# simplefocmini_2022-04-20.net
KiCad netlist of a schematic drawn in Altium Designer
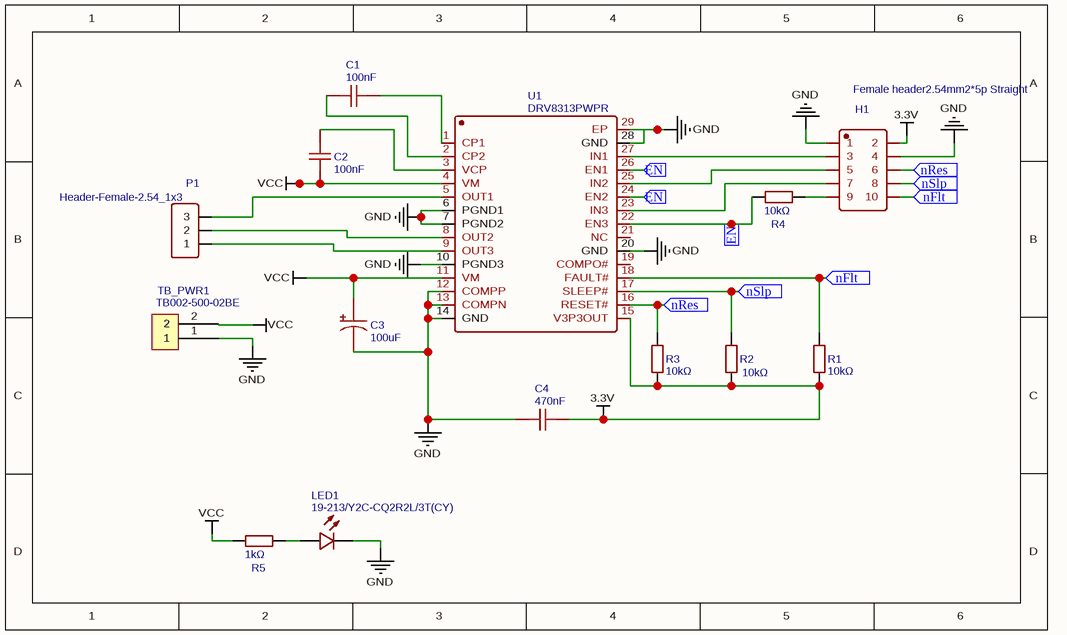
[diagram p0: simplefocmini_2022-04-20.schdoc]

(export (version "E")
  (design (tool "Eeschema 10.0.6"))
  (components
    (comp (ref "C1")
      (value "100nF")
      (fields
        (field (name "BOM_MANUFACTURER PART") "CL10B104KB8NNNC")
        (field (name "BOM_SUPPLIER PART") "C1591")
      )
      (libsource (lib "altium-import") (part "root_0_100nF_"))
    )
    (comp (ref "C2")
      (value "100nF")
      (fields
        (field (name "BOM_MANUFACTURER PART") "CL10B104KB8NNNC")
        (field (name "BOM_SUPPLIER PART") "C1591")
      )
      (libsource (lib "altium-import") (part "root_1_100nF_"))
    )
    (comp (ref "C3")
      (value "100uF")
      (fields
        (field (name "BOM_SUPPLIER PART") "C294520")
        (field (name "BOM_MANUFACTURER PART") "VT1V101M-CRE77")
        (field (name "CONTRIBUTOR") "LCSC")
      )
      (libsource (lib "altium-import") (part "root_0_100uF_"))
    )
    (comp (ref "C4")
      (value "470nF")
      (fields
        (field (name "BOM_SUPPLIER PART") "C327269")
        (field (name "BOM_MANUFACTURER PART") "CC0603ZRY5V6BB474")
        (field (name "CONTRIBUTOR") "LCSC")
      )
      (libsource (lib "altium-import") (part "root_0_470nF_"))
    )
    (comp (ref "H1")
      (value "Female header2.54mm2*5p Straight")
      (fields (field (name "BOM_SUPPLIER PART") "C30419"))
      (libsource (lib "altium-import") (part "root_0_Female header2.54mm2*5p Straight_"))
    )
    (comp (ref "LED1")
      (value "19-213/Y2C-CQ2R2L/3T(CY)")
      (fields (field (name "BOM_SUPPLIER PART") "C72038"))
      (libsource (lib "altium-import") (part "root_0_19-213/Y2C-CQ2R2L/3T(CY)_"))
    )
    (comp (ref "P1")
      (value "Header-Female-2.54_1x3")
      (fields (field (name "BOM_SUPPLIER PART") "C146243"))
      (libsource (lib "altium-import") (part "root_2_Header-Female-2.54_1x3_"))
    )
    (comp (ref "R1")
      (value "10kΩ")
      (fields
        (field (name "BOM_MANUFACTURER PART") "0603WAF4701T5E")
        (field (name "BOM_SUPPLIER PART") "C23162")
      )
      (libsource (lib "altium-import") (part "root_1_10kΩ_"))
    )
    (comp (ref "R2")
      (value "10kΩ")
      (fields
        (field (name "BOM_MANUFACTURER PART") "0603WAF4701T5E")
        (field (name "BOM_SUPPLIER PART") "C23162")
      )
      (libsource (lib "altium-import") (part "root_1_10kΩ_"))
    )
    (comp (ref "R3")
      (value "10kΩ")
      (fields
        (field (name "BOM_MANUFACTURER PART") "0603WAF4701T5E")
        (field (name "BOM_SUPPLIER PART") "C23162")
      )
      (libsource (lib "altium-import") (part "root_1_10kΩ_"))
    )
    (comp (ref "R4")
      (value "10kΩ")
      (fields
        (field (name "BOM_MANUFACTURER PART") "0603WAF4701T5E")
        (field (name "BOM_SUPPLIER PART") "C23162")
      )
      (libsource (lib "altium-import") (part "root_0_10kΩ_"))
    )
    (comp (ref "R5")
      (value "1kΩ")
      (fields
        (field (name "BOM_MANUFACTURER PART") "0603WAF4701T5E")
        (field (name "BOM_SUPPLIER PART") "C23162")
      )
      (libsource (lib "altium-import") (part "root_0_1kΩ_"))
    )
    (comp (ref "TB_PWR1")
      (value "TB002-500-02BE")
      (fields (field (name "CONTRIBUTOR") "the.skuric"))
      (libsource (lib "altium-import") (part "root_0_TB002-500-02BE_"))
    )
    (comp (ref "U1")
      (value "DRV8313PWPR")
      (fields (field (name "BOM_SUPPLIER PART") "C92482") (field (name "CONTRIBUTOR") "LCSC"))
      (libsource (lib "altium-import") (part "root_0_DRV8313PWPR_"))
    )
  )
  (nets
    (net (code "1") (name "/EN") (class "Default")
      (node (ref "R4") (pin "1") (pinfunction "1_1") (pintype "passive"))
      (node (ref "U1") (pin "22") (pinfunction "EN3_22") (pintype "passive"))
      (node (ref "U1") (pin "24") (pinfunction "EN2_24") (pintype "passive"))
      (node (ref "U1") (pin "26") (pinfunction "EN1_26") (pintype "passive"))
    )
    (net (code "2") (name "/nFlt") (class "Default")
      (node (ref "H1") (pin "10") (pinfunction "10_10") (pintype "passive"))
      (node (ref "R1") (pin "2") (pinfunction "2_2") (pintype "passive"))
      (node (ref "U1") (pin "18") (pinfunction "FAULT#_18") (pintype "passive"))
    )
    (net (code "3") (name "/nRes") (class "Default")
      (node (ref "H1") (pin "6") (pinfunction "6_6") (pintype "passive"))
      (node (ref "R3") (pin "2") (pinfunction "2_2") (pintype "passive"))
      (node (ref "U1") (pin "16") (pinfunction "RESET#_16") (pintype "passive"))
    )
    (net (code "4") (name "/nSlp") (class "Default")
      (node (ref "H1") (pin "8") (pinfunction "8_8") (pintype "passive"))
      (node (ref "R2") (pin "2") (pinfunction "2_2") (pintype "passive"))
      (node (ref "U1") (pin "17") (pinfunction "SLEEP#_17") (pintype "passive"))
    )
    (net (code "5") (name "3.3V") (class "Default")
      (node (ref "C4") (pin "2") (pinfunction "2_2") (pintype "passive"))
      (node (ref "H1") (pin "2") (pinfunction "2_2") (pintype "passive"))
      (node (ref "R1") (pin "1") (pinfunction "1_1") (pintype "passive"))
      (node (ref "R2") (pin "1") (pinfunction "1_1") (pintype "passive"))
      (node (ref "R3") (pin "1") (pinfunction "1_1") (pintype "passive"))
      (node (ref "U1") (pin "15") (pinfunction "V3P3OUT_15") (pintype "passive"))
    )
    (net (code "6") (name "GND") (class "Default")
      (node (ref "C3") (pin "2") (pinfunction "2_2") (pintype "passive"))
      (node (ref "C4") (pin "1") (pinfunction "1_1") (pintype "passive"))
      (node (ref "H1") (pin "1") (pinfunction "1_1") (pintype "passive"))
      (node (ref "H1") (pin "4") (pinfunction "4_4") (pintype "passive"))
      (node (ref "LED1") (pin "2") (pinfunction "C_2") (pintype "passive"))
      (node (ref "TB_PWR1") (pin "1") (pinfunction "1_1") (pintype "passive"))
      (node (ref "U1") (pin "10") (pinfunction "PGND3_10") (pintype "passive"))
      (node (ref "U1") (pin "12") (pinfunction "COMPP_12") (pintype "passive"))
      (node (ref "U1") (pin "13") (pinfunction "COMPN_13") (pintype "passive"))
      (node (ref "U1") (pin "14") (pinfunction "GND_14") (pintype "passive"))
      (node (ref "U1") (pin "20") (pinfunction "GND_20") (pintype "passive"))
      (node (ref "U1") (pin "28") (pinfunction "GND_28") (pintype "passive"))
      (node (ref "U1") (pin "29") (pinfunction "EP_29") (pintype "passive"))
      (node (ref "U1") (pin "6") (pinfunction "PGND1_6") (pintype "passive"))
      (node (ref "U1") (pin "7") (pinfunction "PGND2_7") (pintype "passive"))
    )
    (net (code "7") (name "Net-(H1-Pad9)") (class "Default")
      (node (ref "H1") (pin "9") (pinfunction "9_9") (pintype "passive"))
      (node (ref "R4") (pin "2") (pinfunction "2_2") (pintype "passive"))
    )
    (net (code "8") (name "Net-(LED1-A)") (class "Default")
      (node (ref "LED1") (pin "1") (pinfunction "A_1") (pintype "passive"))
      (node (ref "R5") (pin "2") (pinfunction "2_2") (pintype "passive"))
    )
    (net (code "9") (name "Net-(U1-CP1)") (class "Default")
      (node (ref "C1") (pin "2") (pinfunction "2_2") (pintype "passive"))
      (node (ref "U1") (pin "1") (pinfunction "CP1_1") (pintype "passive"))
    )
    (net (code "10") (name "Net-(U1-CP2)") (class "Default")
      (node (ref "C1") (pin "1") (pinfunction "1_1") (pintype "passive"))
      (node (ref "U1") (pin "2") (pinfunction "CP2_2") (pintype "passive"))
    )
    (net (code "11") (name "Net-(U1-IN1)") (class "Default")
      (node (ref "H1") (pin "3") (pinfunction "3_3") (pintype "passive"))
      (node (ref "U1") (pin "27") (pinfunction "IN1_27") (pintype "passive"))
    )
    (net (code "12") (name "Net-(U1-IN2)") (class "Default")
      (node (ref "H1") (pin "5") (pinfunction "5_5") (pintype "passive"))
      (node (ref "U1") (pin "25") (pinfunction "IN2_25") (pintype "passive"))
    )
    (net (code "13") (name "Net-(U1-IN3)") (class "Default")
      (node (ref "H1") (pin "7") (pinfunction "7_7") (pintype "passive"))
      (node (ref "U1") (pin "23") (pinfunction "IN3_23") (pintype "passive"))
    )
    (net (code "14") (name "Net-(U1-OUT1)") (class "Default")
      (node (ref "P1") (pin "3") (pinfunction "3_3") (pintype "passive"))
      (node (ref "U1") (pin "5") (pinfunction "OUT1_5") (pintype "passive"))
    )
    (net (code "15") (name "Net-(U1-OUT2)") (class "Default")
      (node (ref "P1") (pin "2") (pinfunction "2_2") (pintype "passive"))
      (node (ref "U1") (pin "8") (pinfunction "OUT2_8") (pintype "passive"))
    )
    (net (code "16") (name "Net-(U1-OUT3)") (class "Default")
      (node (ref "P1") (pin "1") (pinfunction "1_1") (pintype "passive"))
      (node (ref "U1") (pin "9") (pinfunction "OUT3_9") (pintype "passive"))
    )
    (net (code "17") (name "Net-(U1-VCP)") (class "Default")
      (node (ref "C2") (pin "2") (pinfunction "2_2") (pintype "passive"))
      (node (ref "U1") (pin "3") (pinfunction "VCP_3") (pintype "passive"))
    )
    (net (code "18") (name "VCC") (class "Default")
      (node (ref "C2") (pin "1") (pinfunction "1_1") (pintype "passive"))
      (node (ref "C3") (pin "1") (pinfunction "1_1") (pintype "passive"))
      (node (ref "R5") (pin "1") (pinfunction "1_1") (pintype "passive"))
      (node (ref "TB_PWR1") (pin "2") (pinfunction "2_2") (pintype "passive"))
      (node (ref "U1") (pin "11") (pinfunction "VM_11") (pintype "passive"))
      (node (ref "U1") (pin "4") (pinfunction "VM_4") (pintype "passive"))
    )
    (net (code "19") (name "unconnected-(U1-COMPO#-Pad19)") (class "Default")
      (node (ref "U1") (pin "19") (pinfunction "COMPO#_19") (pintype "passive"))
    )
    (net (code "20") (name "unconnected-(U1-NC-Pad21)") (class "Default")
      (node (ref "U1") (pin "21") (pinfunction "NC_21") (pintype "passive"))
    )
  )
)
